# Sheet1.net
KiCad netlist of a schematic drawn in Altium Designer
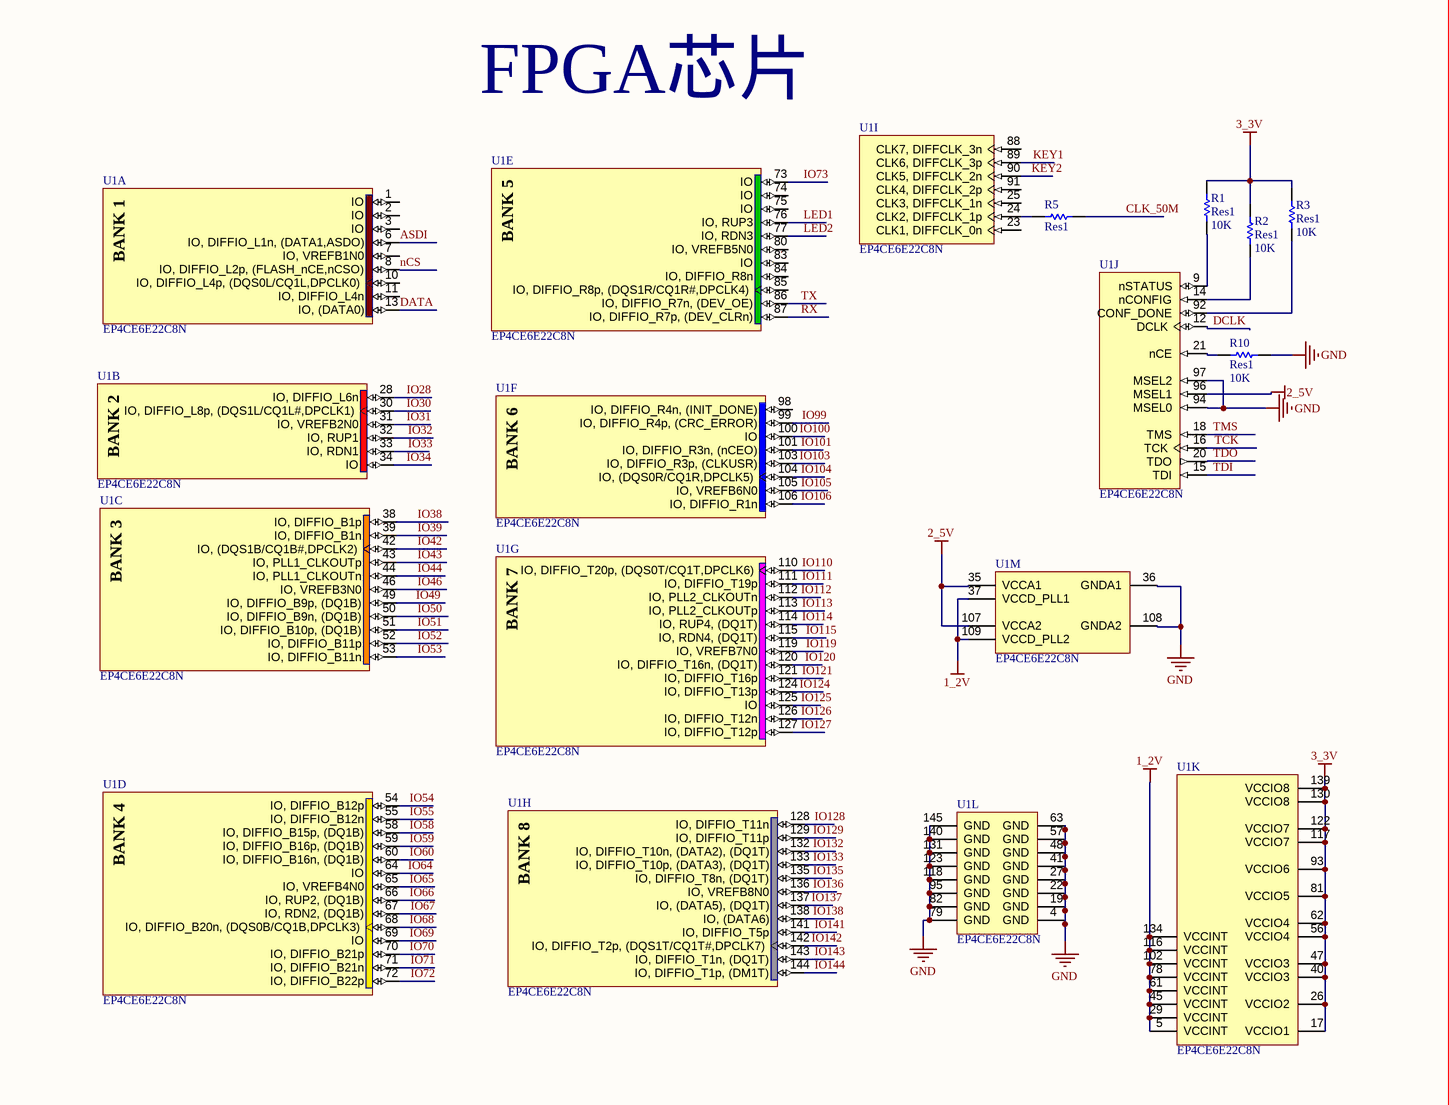
[diagram p0: Sheet1.SchDoc, top left]
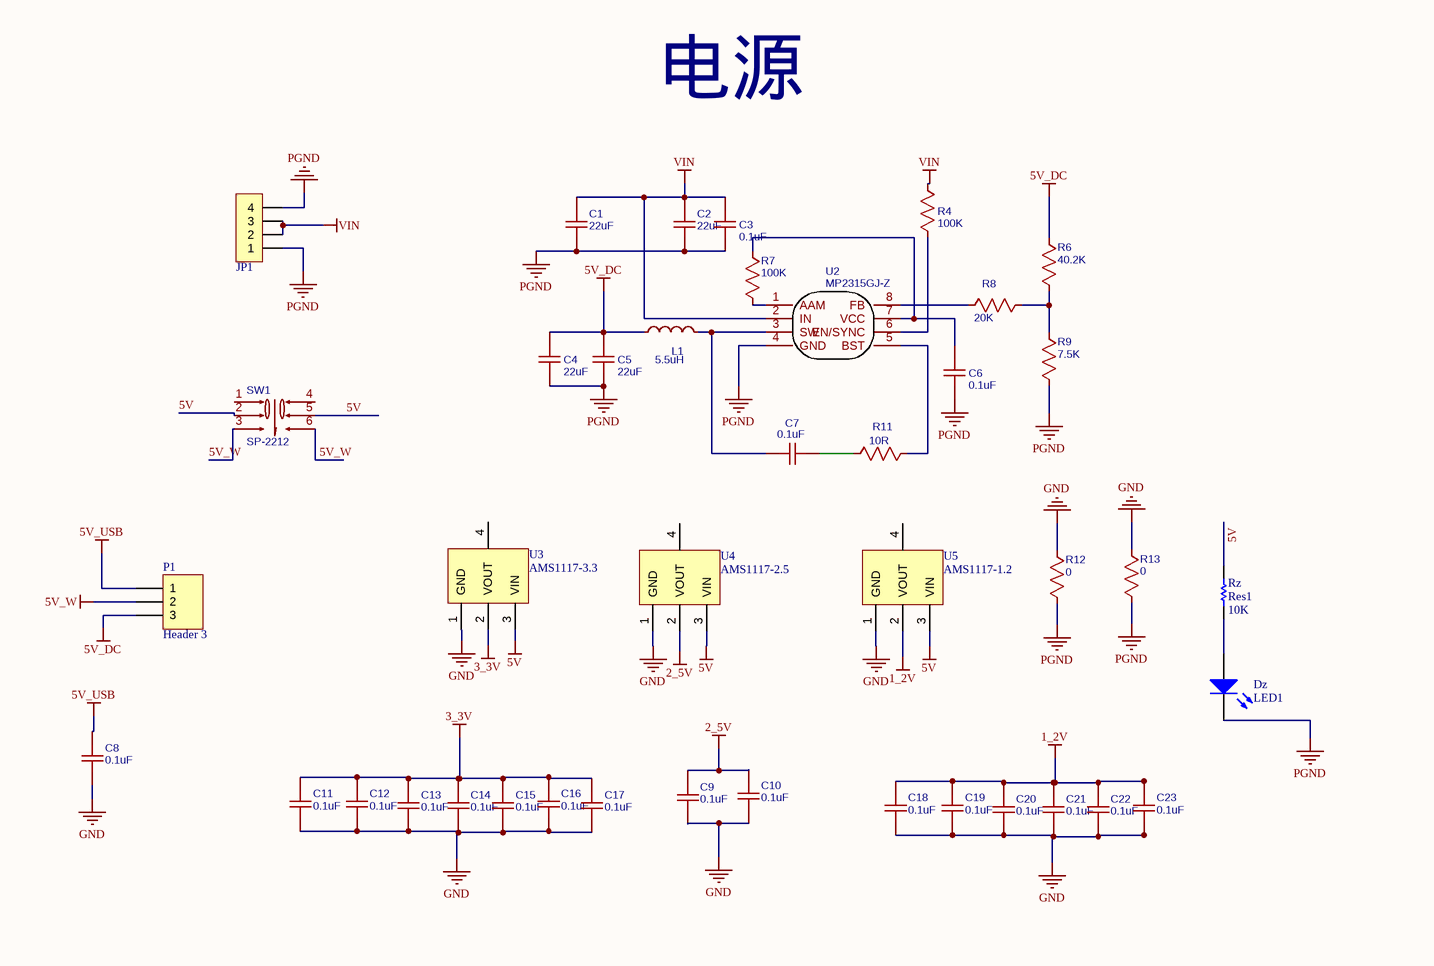
[diagram p1: Sheet1.SchDoc, top right]
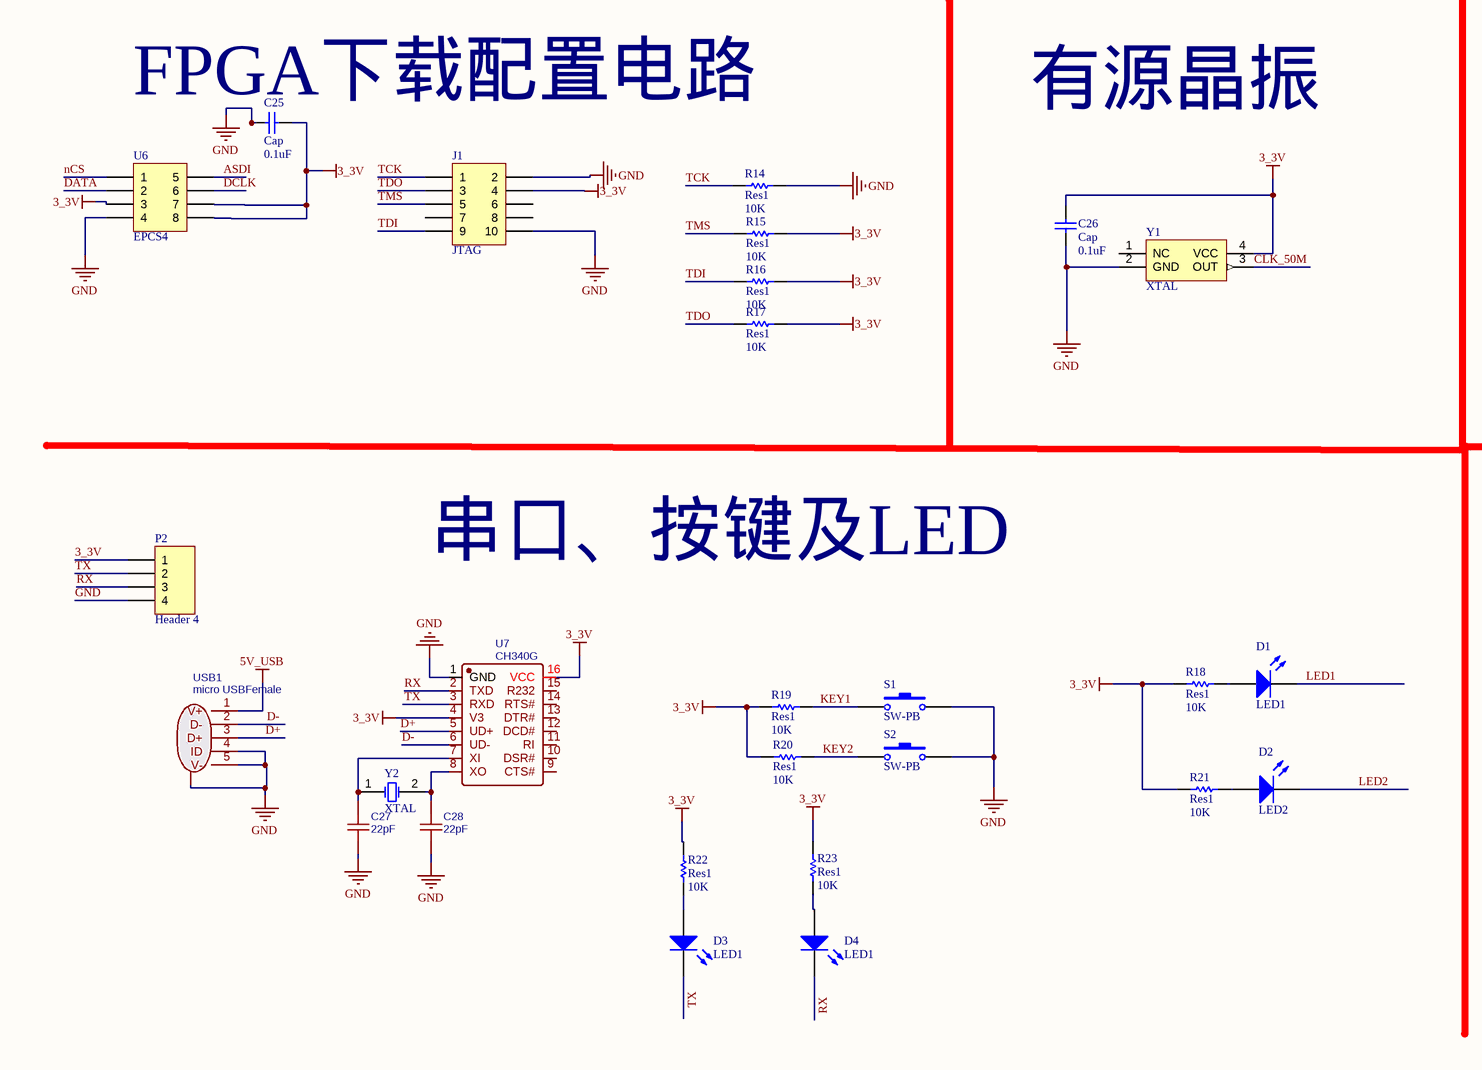
[diagram p2: Sheet1.SchDoc, bottom left]
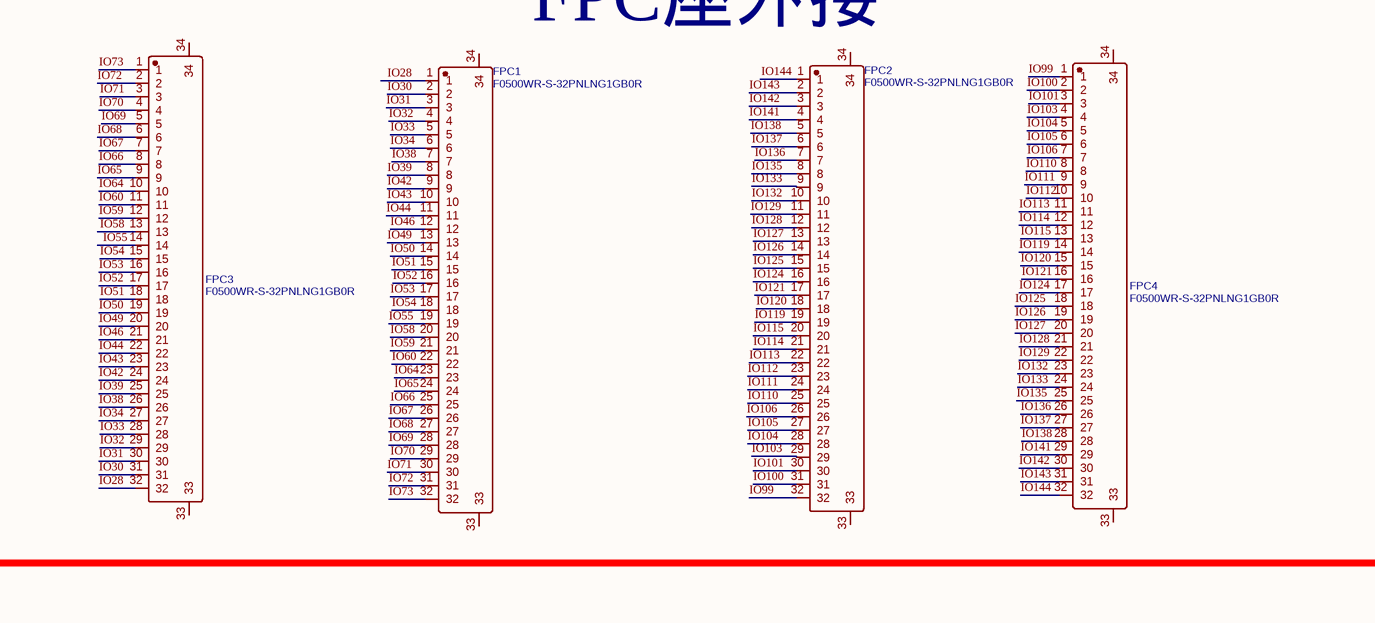
[diagram p3: Sheet1.SchDoc, bottom right]

(export (version "E")
  (design (tool "Eeschema 10.0.6"))
  (components
    (comp (ref "C1")
      (value "22uF")
      (footprint "C 0805_M")
      (fields (field (name "CONTRIBUTOR") "LCEDA_Lib"))
      (libsource (lib "altium-import") (part "root_3_22uF_"))
    )
    (comp (ref "C2")
      (value "22uF")
      (footprint "C 0603_M")
      (fields (field (name "CONTRIBUTOR") "LCEDA_Lib"))
      (libsource (lib "altium-import") (part "root_3_22uF_"))
    )
    (comp (ref "C3")
      (value "0.1uF")
      (footprint "C 0805_M")
      (fields (field (name "CONTRIBUTOR") "LCEDA_Lib"))
      (libsource (lib "altium-import") (part "root_1_0.1uF_"))
    )
    (comp (ref "C4")
      (value "22uF")
      (footprint "C 0805_M")
      (fields (field (name "CONTRIBUTOR") "LCEDA_Lib"))
      (libsource (lib "altium-import") (part "root_1_22uF_"))
    )
    (comp (ref "C5")
      (value "22uF")
      (footprint "C 0805_M")
      (fields (field (name "CONTRIBUTOR") "LCEDA_Lib"))
      (libsource (lib "altium-import") (part "root_1_22uF_"))
    )
    (comp (ref "C6")
      (value "0.1uF")
      (footprint "C 0603_M")
      (fields (field (name "CONTRIBUTOR") "LCEDA_Lib"))
      (libsource (lib "altium-import") (part "root_1_0.1uF_"))
    )
    (comp (ref "C7")
      (value "0.1uF")
      (footprint "C 0805_M")
      (fields (field (name "CONTRIBUTOR") "LCEDA_Lib"))
      (libsource (lib "altium-import") (part "root_0_0.1uF_"))
    )
    (comp (ref "C8")
      (value "0.1uF")
      (footprint "C 0805_M")
      (fields (field (name "CONTRIBUTOR") "LCEDA_Lib"))
      (libsource (lib "altium-import") (part "root_1_0.1uF_"))
    )
    (comp (ref "C9")
      (value "0.1uF")
      (footprint "C 0603_M")
      (fields (field (name "CONTRIBUTOR") "LCEDA_Lib"))
      (libsource (lib "altium-import") (part "root_1_0.1uF_"))
    )
    (comp (ref "C10")
      (value "0.1uF")
      (footprint "C 0603_M")
      (fields (field (name "CONTRIBUTOR") "LCEDA_Lib"))
      (libsource (lib "altium-import") (part "root_1_0.1uF_"))
    )
    (comp (ref "C11")
      (value "0.1uF")
      (footprint "C 0603_M")
      (fields (field (name "CONTRIBUTOR") "LCEDA_Lib"))
      (libsource (lib "altium-import") (part "root_1_0.1uF_"))
    )
    (comp (ref "C12")
      (value "0.1uF")
      (footprint "C 0603_M")
      (fields (field (name "CONTRIBUTOR") "LCEDA_Lib"))
      (libsource (lib "altium-import") (part "root_1_0.1uF_"))
    )
    (comp (ref "C13")
      (value "0.1uF")
      (footprint "C 0603_M")
      (fields (field (name "CONTRIBUTOR") "LCEDA_Lib"))
      (libsource (lib "altium-import") (part "root_1_0.1uF_"))
    )
    (comp (ref "C14")
      (value "0.1uF")
      (footprint "C 0603_M")
      (fields (field (name "CONTRIBUTOR") "LCEDA_Lib"))
      (libsource (lib "altium-import") (part "root_1_0.1uF_"))
    )
    (comp (ref "C15")
      (value "0.1uF")
      (footprint "C 0603_M")
      (fields (field (name "CONTRIBUTOR") "LCEDA_Lib"))
      (libsource (lib "altium-import") (part "root_1_0.1uF_"))
    )
    (comp (ref "C16")
      (value "0.1uF")
      (footprint "C 0603_M")
      (fields (field (name "CONTRIBUTOR") "LCEDA_Lib"))
      (libsource (lib "altium-import") (part "root_1_0.1uF_"))
    )
    (comp (ref "C17")
      (value "0.1uF")
      (footprint "C 0603_M")
      (fields (field (name "CONTRIBUTOR") "LCEDA_Lib"))
      (libsource (lib "altium-import") (part "root_1_0.1uF_"))
    )
    (comp (ref "C18")
      (value "0.1uF")
      (footprint "C 0603_M")
      (fields (field (name "CONTRIBUTOR") "LCEDA_Lib"))
      (libsource (lib "altium-import") (part "root_1_0.1uF_"))
    )
    (comp (ref "C19")
      (value "0.1uF")
      (footprint "C 0603_M")
      (fields (field (name "CONTRIBUTOR") "LCEDA_Lib"))
      (libsource (lib "altium-import") (part "root_1_0.1uF_"))
    )
    (comp (ref "C20")
      (value "0.1uF")
      (footprint "C 0603_M")
      (fields (field (name "CONTRIBUTOR") "LCEDA_Lib"))
      (libsource (lib "altium-import") (part "root_1_0.1uF_"))
    )
    (comp (ref "C21")
      (value "0.1uF")
      (footprint "C 0603_M")
      (fields (field (name "CONTRIBUTOR") "LCEDA_Lib"))
      (libsource (lib "altium-import") (part "root_1_0.1uF_"))
    )
    (comp (ref "C22")
      (value "0.1uF")
      (footprint "C 0603_M")
      (fields (field (name "CONTRIBUTOR") "LCEDA_Lib"))
      (libsource (lib "altium-import") (part "root_1_0.1uF_"))
    )
    (comp (ref "C23")
      (value "0.1uF")
      (footprint "C 0603_M")
      (fields (field (name "CONTRIBUTOR") "LCEDA_Lib"))
      (libsource (lib "altium-import") (part "root_1_0.1uF_"))
    )
    (comp (ref "C25")
      (value "Cap")
      (footprint "C 0805_M")
      (description "Capacitor")
      (fields (field (name "ALTIUM_VALUE") "0.1uF") (field (name "PUBLISHER") "Altium Limited"))
      (libsource (lib "Miscellaneous Devices") (part "Cap"))
    )
    (comp (ref "C26")
      (value "Cap")
      (footprint "C 0805_M")
      (description "Capacitor")
      (fields (field (name "ALTIUM_VALUE") "0.1uF") (field (name "PUBLISHER") "Altium Limited"))
      (libsource (lib "Miscellaneous Devices") (part "Cap"))
    )
    (comp (ref "C27")
      (value "22pF")
      (footprint "C 0603_M")
      (fields (field (name "CONTRIBUTOR") "LCEDA_Lib"))
      (libsource (lib "altium-import") (part "root_1_0.1uF_"))
    )
    (comp (ref "C28")
      (value "22pF")
      (footprint "C 0603_M")
      (fields (field (name "CONTRIBUTOR") "LCEDA_Lib"))
      (libsource (lib "altium-import") (part "root_1_0.1uF_"))
    )
    (comp (ref "D1")
      (value "LED1")
      (footprint "LED-0805")
      (description "Typical INFRARED GaAs LED")
      (fields (field (name "PUBLISHER") "Altium Limited"))
      (libsource (lib "Miscellaneous Devices") (part "LED0"))
    )
    (comp (ref "D2")
      (value "LED2")
      (footprint "LED-0805")
      (description "Typical INFRARED GaAs LED")
      (fields (field (name "PUBLISHER") "Altium Limited"))
      (libsource (lib "Miscellaneous Devices") (part "LED0"))
    )
    (comp (ref "D3")
      (value "LED1")
      (footprint "LED-0805")
      (description "Typical INFRARED GaAs LED")
      (fields (field (name "PUBLISHER") "Altium Limited"))
      (libsource (lib "Miscellaneous Devices") (part "LED0"))
    )
    (comp (ref "D4")
      (value "LED1")
      (footprint "LED-0805")
      (description "Typical INFRARED GaAs LED")
      (fields (field (name "PUBLISHER") "Altium Limited"))
      (libsource (lib "Miscellaneous Devices") (part "LED0"))
    )
    (comp (ref "Dz")
      (value "LED1")
      (footprint "LED-0805")
      (description "Typical INFRARED GaAs LED")
      (fields (field (name "PUBLISHER") "Altium Limited"))
      (libsource (lib "Miscellaneous Devices") (part "LED0"))
    )
    (comp (ref "FPC1")
      (value "F0500WR-S-32PNLNG1GB0R")
      (footprint "FPC0.5 2H-WS-32P")
      (fields (field (name "BOM_SUPPLIER PART") "C247880") (field (name "CONTRIBUTOR") "LCSC"))
      (libsource (lib "altium-import") (part "root_0_F0500WR-S-32PNLNG1GB0R_"))
    )
    (comp (ref "FPC2")
      (value "F0500WR-S-32PNLNG1GB0R")
      (footprint "FPC0.5 2H-WS-32P")
      (fields (field (name "BOM_SUPPLIER PART") "C247880") (field (name "CONTRIBUTOR") "LCSC"))
      (libsource (lib "altium-import") (part "root_0_F0500WR-S-32PNLNG1GB0R_"))
    )
    (comp (ref "FPC3")
      (value "F0500WR-S-32PNLNG1GB0R")
      (footprint "FPC0.5 2H-WS-32P")
      (fields (field (name "BOM_SUPPLIER PART") "C247880") (field (name "CONTRIBUTOR") "LCSC"))
      (libsource (lib "altium-import") (part "root_0_F0500WR-S-32PNLNG1GB0R_"))
    )
    (comp (ref "FPC4")
      (value "F0500WR-S-32PNLNG1GB0R")
      (footprint "FPC0.5 2H-WS-32P")
      (fields (field (name "BOM_SUPPLIER PART") "C247880") (field (name "CONTRIBUTOR") "LCSC"))
      (libsource (lib "altium-import") (part "root_0_F0500WR-S-32PNLNG1GB0R_"))
    )
    (comp (ref "J1")
      (value "JTAG")
      (footprint "牛角座10p")
      (description "Header, 5-Pin, Dual row, Right Angle")
      (fields (field (name "PUBLISHER") "Altium Limited"))
      (libsource (lib "Miscellaneous Connectors") (part "Header 5X2H"))
    )
    (comp (ref "JP1")
      (value "HDR-1X4")
      (footprint "KF128-5.08-4P")
      (description "4P接插件")
      (fields (field (name "版权归属") "封装库来自淘宝卖家 ID：黄晶宝石"))
      (libsource (lib "6.1 - 接插件-脚距5.08 (200mil) ") (part "Header 4"))
    )
    (comp (ref "L1")
      (value "5.5uH")
      (footprint "L-SMD-0630")
      (fields
        (field (name "BOM_SUPPLIER PART") "C268387")
        (field (name "BOM_MANUFACTURER PART") "MPCA-0624-4R7-M")
        (field (name "CONTRIBUTOR") "LCSC")
      )
      (libsource (lib "altium-import") (part "root_0_4.7uH_"))
    )
    (comp (ref "P1")
      (value "Header 3")
      (footprint "HDR1X3")
      (description "Header, 3-Pin")
      (fields (field (name "PUBLISHER") "Altium Limited"))
      (libsource (lib "Miscellaneous Connectors") (part "Header 3"))
    )
    (comp (ref "P2")
      (value "Header 4")
      (footprint "HDR1X4")
      (description "Header, 4-Pin")
      (fields (field (name "PUBLISHER") "Altium Limited"))
      (libsource (lib "Miscellaneous Connectors") (part "Header 4"))
    )
    (comp (ref "R1")
      (value "Res1")
      (footprint "R 0603_M")
      (description "Resistor")
      (fields (field (name "ALTIUM_VALUE") "10K") (field (name "PUBLISHER") "Altium Limited"))
      (libsource (lib "Miscellaneous Devices") (part "Res1"))
    )
    (comp (ref "R2")
      (value "Res1")
      (footprint "R 0603_M")
      (description "Resistor")
      (fields (field (name "ALTIUM_VALUE") "10K") (field (name "PUBLISHER") "Altium Limited"))
      (libsource (lib "Miscellaneous Devices") (part "Res1"))
    )
    (comp (ref "R3")
      (value "Res1")
      (footprint "R 0603_M")
      (description "Resistor")
      (fields (field (name "ALTIUM_VALUE") "10K") (field (name "PUBLISHER") "Altium Limited"))
      (libsource (lib "Miscellaneous Devices") (part "Res1"))
    )
    (comp (ref "R4")
      (value "100K")
      (footprint "R 0603_M")
      (fields (field (name "CONTRIBUTOR") "LCEDA_Lib"))
      (libsource (lib "altium-import") (part "root_1_100K_"))
    )
    (comp (ref "R5")
      (value "Res1")
      (footprint "R 0603_M")
      (description "Resistor")
      (fields (field (name "PUBLISHER") "Altium Limited"))
      (libsource (lib "Miscellaneous Devices") (part "Res1"))
    )
    (comp (ref "R6")
      (value "40.2K")
      (footprint "R 0603_M")
      (fields (field (name "CONTRIBUTOR") "LCEDA_Lib"))
      (libsource (lib "altium-import") (part "root_3_10R_"))
    )
    (comp (ref "R7")
      (value "100K")
      (footprint "R 0603_M")
      (fields (field (name "CONTRIBUTOR") "LCEDA_Lib"))
      (libsource (lib "altium-import") (part "root_3_7.5k_"))
    )
    (comp (ref "R8")
      (value "20K")
      (footprint "R 0603_M")
      (fields (field (name "CONTRIBUTOR") "LCEDA_Lib"))
      (libsource (lib "altium-import") (part "root_2_10R_"))
    )
    (comp (ref "R9")
      (value "7.5K")
      (footprint "R 0603_M")
      (fields (field (name "CONTRIBUTOR") "LCEDA_Lib"))
      (libsource (lib "altium-import") (part "root_3_10R_"))
    )
    (comp (ref "R10")
      (value "Res1")
      (footprint "R 0603_M")
      (description "Resistor")
      (fields (field (name "ALTIUM_VALUE") "10K") (field (name "PUBLISHER") "Altium Limited"))
      (libsource (lib "Miscellaneous Devices") (part "Res1"))
    )
    (comp (ref "R11")
      (value "10R")
      (footprint "R 0603_M")
      (fields (field (name "CONTRIBUTOR") "LCEDA_Lib"))
      (libsource (lib "altium-import") (part "root_2_10R_"))
    )
    (comp (ref "R12")
      (value "0")
      (footprint "R 0603_M")
      (fields (field (name "CONTRIBUTOR") "LCEDA_Lib"))
      (libsource (lib "altium-import") (part "root_3_10R_"))
    )
    (comp (ref "R13")
      (value "0")
      (footprint "R 0603_M")
      (fields (field (name "CONTRIBUTOR") "LCEDA_Lib"))
      (libsource (lib "altium-import") (part "root_3_10R_"))
    )
    (comp (ref "R14")
      (value "Res1")
      (footprint "R 0603_M")
      (description "Resistor")
      (fields (field (name "ALTIUM_VALUE") "10K") (field (name "PUBLISHER") "Altium Limited"))
      (libsource (lib "Miscellaneous Devices") (part "Res1"))
    )
    (comp (ref "R15")
      (value "Res1")
      (footprint "R 0603_M")
      (description "Resistor")
      (fields (field (name "ALTIUM_VALUE") "10K") (field (name "PUBLISHER") "Altium Limited"))
      (libsource (lib "Miscellaneous Devices") (part "Res1"))
    )
    (comp (ref "R16")
      (value "Res1")
      (footprint "R 0603_M")
      (description "Resistor")
      (fields (field (name "ALTIUM_VALUE") "10K") (field (name "PUBLISHER") "Altium Limited"))
      (libsource (lib "Miscellaneous Devices") (part "Res1"))
    )
    (comp (ref "R17")
      (value "Res1")
      (footprint "R 0603_M")
      (description "Resistor")
      (fields (field (name "ALTIUM_VALUE") "10K") (field (name "PUBLISHER") "Altium Limited"))
      (libsource (lib "Miscellaneous Devices") (part "Res1"))
    )
    (comp (ref "R18")
      (value "Res1")
      (footprint "R 0603_M")
      (description "Resistor")
      (fields (field (name "ALTIUM_VALUE") "10K") (field (name "PUBLISHER") "Altium Limited"))
      (libsource (lib "Miscellaneous Devices") (part "Res1"))
    )
    (comp (ref "R19")
      (value "Res1")
      (footprint "R 0603_M")
      (description "Resistor")
      (fields (field (name "ALTIUM_VALUE") "10K") (field (name "PUBLISHER") "Altium Limited"))
      (libsource (lib "Miscellaneous Devices") (part "Res1"))
    )
    (comp (ref "R20")
      (value "Res1")
      (footprint "R 0603_M")
      (description "Resistor")
      (fields (field (name "ALTIUM_VALUE") "10K") (field (name "PUBLISHER") "Altium Limited"))
      (libsource (lib "Miscellaneous Devices") (part "Res1"))
    )
    (comp (ref "R21")
      (value "Res1")
      (footprint "R 0603_M")
      (description "Resistor")
      (fields (field (name "ALTIUM_VALUE") "10K") (field (name "PUBLISHER") "Altium Limited"))
      (libsource (lib "Miscellaneous Devices") (part "Res1"))
    )
    (comp (ref "R22")
      (value "Res1")
      (footprint "R 0603_M")
      (description "Resistor")
      (fields (field (name "ALTIUM_VALUE") "10K") (field (name "PUBLISHER") "Altium Limited"))
      (libsource (lib "Miscellaneous Devices") (part "Res1"))
    )
    (comp (ref "R23")
      (value "Res1")
      (footprint "R 0603_M")
      (description "Resistor")
      (fields (field (name "ALTIUM_VALUE") "10K") (field (name "PUBLISHER") "Altium Limited"))
      (libsource (lib "Miscellaneous Devices") (part "Res1"))
    )
    (comp (ref "Rz")
      (value "Res1")
      (footprint "R 0603_M")
      (description "Resistor")
      (fields (field (name "ALTIUM_VALUE") "10K") (field (name "PUBLISHER") "Altium Limited"))
      (libsource (lib "Miscellaneous Devices") (part "Res1"))
    )
    (comp (ref "S1")
      (value "SW-PB")
      (footprint "SPST4")
      (description "Switch")
      (fields (field (name "PUBLISHER") "Altium Limited"))
      (libsource (lib "我的元件库") (part "SW-PB"))
    )
    (comp (ref "S2")
      (value "SW-PB")
      (footprint "SPST4")
      (description "Switch")
      (fields (field (name "PUBLISHER") "Altium Limited"))
      (libsource (lib "我的元件库") (part "SW-PB"))
    )
    (comp (ref "SW1")
      (value "SP-2212")
      (footprint "自锁开关")
      (fields (field (name "BOM_SUPPLIER PART") "C589287") (field (name "CONTRIBUTOR") "LCSC"))
      (libsource (lib "altium-import") (part "root_3_SP-2212_"))
    )
    (comp (ref "U1")
      (value "EP4CE6E22C8N")
      (footprint "EQFP144_A-165_D2-54_N")
      (fields (field (name "MANUFACTURER") "Altera"))
      (libsource (lib "Altera Cyclone IV E") (part "EP4CE6E22C8N"))
    )
    (comp (ref "U2")
      (value "MP2315GJ-Z")
      (footprint "SOT23-8N")
      (fields (field (name "BOM_SUPPLIER PART") "C45889"))
      (libsource (lib "altium-import") (part "root_0_MP2315GJ-Z_"))
    )
    (comp (ref "U3")
      (value "AMS1117-3.3")
      (footprint "SOT223_N")
      (description "3.3Voutput,4.3-12Vinput LDO")
      (libsource (lib "我的元件库") (part "AMS1117"))
    )
    (comp (ref "U4")
      (value "AMS1117-2.5")
      (footprint "SOT223_N")
      (description "3.3Voutput,4.3-12Vinput LDO")
      (libsource (lib "我的元件库") (part "AMS1117"))
    )
    (comp (ref "U5")
      (value "AMS1117-1.2")
      (footprint "SOT223_N")
      (description "3.3Voutput,4.3-12Vinput LDO")
      (libsource (lib "我的元件库") (part "AMS1117"))
    )
    (comp (ref "U6")
      (value "EPCS4")
      (footprint "SOP8")
      (description "Header, 4-Pin, Dual row")
      (fields (field (name "PUBLISHER") "Altium Limited"))
      (libsource (lib "Miscellaneous Connectors") (part "Header 4X2A"))
    )
    (comp (ref "U7")
      (value "CH340G")
      (footprint "SOIC-16_L9.9-W3.9-P1.27-LS6.0-BL")
      (fields (field (name "BOM_SUPPLIER PART") "C14267"))
      (libsource (lib "altium-import") (part "root_0_CH340G_"))
    )
    (comp (ref "USB1")
      (value "micro USBFemale")
      (footprint "MICRO-USB-SMD_5P-P0.65-H-F_C10418")
      (fields (field (name "BOM_SUPPLIER PART") "C10418"))
      (libsource (lib "altium-import") (part "root_0_micro USBFemale_"))
    )
    (comp (ref "Y1")
      (value "XTAL")
      (footprint "OSC-SMD_4P-L7.0-W5.0-BL")
      (libsource (lib "我的元件库") (part "有源晶振"))
    )
    (comp (ref "Y2")
      (value "XTAL")
      (footprint "标准晶振")
      (description "Crystal Oscillator")
      (fields (field (name "PUBLISHER") "Altium Limited"))
      (libsource (lib "Miscellaneous Devices") (part "XTAL"))
    )
  )
  (nets
    (net (code "1") (name "/ASDI") (class "Default")
      (node (ref "U1") (pin "6") (pinfunction "IO,_DIFFIO_L1n,_(DATA1,ASDO)_6") (pintype "bidirectional"))
      (node (ref "U6") (pin "5") (pinfunction "5_5") (pintype "passive"))
    )
    (net (code "2") (name "/CLK_50M") (class "Default")
      (node (ref "R5") (pin "2") (pinfunction "2_2") (pintype "passive"))
      (node (ref "Y1") (pin "3") (pinfunction "OUT_3") (pintype "output"))
    )
    (net (code "3") (name "/D+") (class "Default")
      (node (ref "U7") (pin "5") (pinfunction "UD+_5") (pintype "passive"))
      (node (ref "USB1") (pin "3") (pinfunction "D+_3") (pintype "passive"))
    )
    (net (code "4") (name "/D-") (class "Default")
      (node (ref "U7") (pin "6") (pinfunction "UD-_6") (pintype "passive"))
      (node (ref "USB1") (pin "2") (pinfunction "D-_2") (pintype "passive"))
    )
    (net (code "5") (name "/DATA") (class "Default")
      (node (ref "U1") (pin "13") (pinfunction "IO,_(DATA0)_13") (pintype "bidirectional"))
      (node (ref "U6") (pin "2") (pinfunction "2_2") (pintype "passive"))
    )
    (net (code "6") (name "/DCLK") (class "Default")
      (node (ref "U1") (pin "12") (pinfunction "DCLK_12") (pintype "bidirectional"))
      (node (ref "U6") (pin "6") (pinfunction "6_6") (pintype "passive"))
    )
    (net (code "7") (name "/IO28") (class "Default")
      (node (ref "FPC1") (pin "1") (pinfunction "1_1") (pintype "passive"))
      (node (ref "FPC3") (pin "32") (pinfunction "32_32") (pintype "passive"))
      (node (ref "U1") (pin "28") (pinfunction "IO,_DIFFIO_L6n_28") (pintype "bidirectional"))
    )
    (net (code "8") (name "/IO30") (class "Default")
      (node (ref "FPC1") (pin "2") (pinfunction "2_2") (pintype "passive"))
      (node (ref "FPC3") (pin "31") (pinfunction "31_31") (pintype "passive"))
      (node (ref "U1") (pin "30") (pinfunction "IO,_DIFFIO_L8p,_(DQS1L/CQ1L#,DPCLK1)_30") (pintype "bidirectional"))
    )
    (net (code "9") (name "/IO31") (class "Default")
      (node (ref "FPC1") (pin "3") (pinfunction "3_3") (pintype "passive"))
      (node (ref "FPC3") (pin "30") (pinfunction "30_30") (pintype "passive"))
      (node (ref "U1") (pin "31") (pinfunction "IO,_VREFB2N0_31") (pintype "bidirectional"))
    )
    (net (code "10") (name "/IO32") (class "Default")
      (node (ref "FPC1") (pin "4") (pinfunction "4_4") (pintype "passive"))
      (node (ref "FPC3") (pin "29") (pinfunction "29_29") (pintype "passive"))
      (node (ref "U1") (pin "32") (pinfunction "IO,_RUP1_32") (pintype "bidirectional"))
    )
    (net (code "11") (name "/IO33") (class "Default")
      (node (ref "FPC1") (pin "5") (pinfunction "5_5") (pintype "passive"))
      (node (ref "FPC3") (pin "28") (pinfunction "28_28") (pintype "passive"))
      (node (ref "U1") (pin "33") (pinfunction "IO,_RDN1_33") (pintype "bidirectional"))
    )
    (net (code "12") (name "/IO34") (class "Default")
      (node (ref "FPC1") (pin "6") (pinfunction "6_6") (pintype "passive"))
      (node (ref "FPC3") (pin "27") (pinfunction "27_27") (pintype "passive"))
      (node (ref "U1") (pin "34") (pinfunction "IO_34") (pintype "bidirectional"))
    )
    (net (code "13") (name "/IO38") (class "Default")
      (node (ref "FPC1") (pin "7") (pinfunction "7_7") (pintype "passive"))
      (node (ref "FPC3") (pin "26") (pinfunction "26_26") (pintype "passive"))
      (node (ref "U1") (pin "38") (pinfunction "IO,_DIFFIO_B1p_38") (pintype "bidirectional"))
    )
    (net (code "14") (name "/IO39") (class "Default")
      (node (ref "FPC1") (pin "8") (pinfunction "8_8") (pintype "passive"))
      (node (ref "FPC3") (pin "25") (pinfunction "25_25") (pintype "passive"))
      (node (ref "U1") (pin "39") (pinfunction "IO,_DIFFIO_B1n_39") (pintype "bidirectional"))
    )
    (net (code "15") (name "/IO42") (class "Default")
      (node (ref "FPC1") (pin "9") (pinfunction "9_9") (pintype "passive"))
      (node (ref "FPC3") (pin "24") (pinfunction "24_24") (pintype "passive"))
      (node (ref "U1") (pin "42") (pinfunction "IO,_(DQS1B/CQ1B#,DPCLK2)_42") (pintype "bidirectional"))
    )
    (net (code "16") (name "/IO43") (class "Default")
      (node (ref "FPC1") (pin "10") (pinfunction "10_10") (pintype "passive"))
      (node (ref "FPC3") (pin "23") (pinfunction "23_23") (pintype "passive"))
      (node (ref "U1") (pin "43") (pinfunction "IO,_PLL1_CLKOUTp_43") (pintype "bidirectional"))
    )
    (net (code "17") (name "/IO44") (class "Default")
      (node (ref "FPC1") (pin "11") (pinfunction "11_11") (pintype "passive"))
      (node (ref "FPC3") (pin "22") (pinfunction "22_22") (pintype "passive"))
      (node (ref "U1") (pin "44") (pinfunction "IO,_PLL1_CLKOUTn_44") (pintype "bidirectional"))
    )
    (net (code "18") (name "/IO46") (class "Default")
      (node (ref "FPC1") (pin "12") (pinfunction "12_12") (pintype "passive"))
      (node (ref "FPC3") (pin "21") (pinfunction "21_21") (pintype "passive"))
      (node (ref "U1") (pin "46") (pinfunction "IO,_VREFB3N0_46") (pintype "bidirectional"))
    )
    (net (code "19") (name "/IO49") (class "Default")
      (node (ref "FPC1") (pin "13") (pinfunction "13_13") (pintype "passive"))
      (node (ref "FPC3") (pin "20") (pinfunction "20_20") (pintype "passive"))
      (node (ref "U1") (pin "49") (pinfunction "IO,_DIFFIO_B9p,_(DQ1B)_49") (pintype "bidirectional"))
    )
    (net (code "20") (name "/IO50") (class "Default")
      (node (ref "FPC1") (pin "14") (pinfunction "14_14") (pintype "passive"))
      (node (ref "FPC3") (pin "19") (pinfunction "19_19") (pintype "passive"))
      (node (ref "U1") (pin "50") (pinfunction "IO,_DIFFIO_B9n,_(DQ1B)_50") (pintype "bidirectional"))
    )
    (net (code "21") (name "/IO51") (class "Default")
      (node (ref "FPC1") (pin "15") (pinfunction "15_15") (pintype "passive"))
      (node (ref "FPC3") (pin "18") (pinfunction "18_18") (pintype "passive"))
      (node (ref "U1") (pin "51") (pinfunction "IO,_DIFFIO_B10p,_(DQ1B)_51") (pintype "bidirectional"))
    )
    (net (code "22") (name "/IO52") (class "Default")
      (node (ref "FPC1") (pin "16") (pinfunction "16_16") (pintype "passive"))
      (node (ref "FPC3") (pin "17") (pinfunction "17_17") (pintype "passive"))
      (node (ref "U1") (pin "52") (pinfunction "IO,_DIFFIO_B11p_52") (pintype "bidirectional"))
    )
    (net (code "23") (name "/IO53") (class "Default")
      (node (ref "FPC1") (pin "17") (pinfunction "17_17") (pintype "passive"))
      (node (ref "FPC3") (pin "16") (pinfunction "16_16") (pintype "passive"))
      (node (ref "U1") (pin "53") (pinfunction "IO,_DIFFIO_B11n_53") (pintype "bidirectional"))
    )
    (net (code "24") (name "/IO54") (class "Default")
      (node (ref "FPC1") (pin "18") (pinfunction "18_18") (pintype "passive"))
      (node (ref "FPC3") (pin "15") (pinfunction "15_15") (pintype "passive"))
      (node (ref "U1") (pin "54") (pinfunction "IO,_DIFFIO_B12p_54") (pintype "bidirectional"))
    )
    (net (code "25") (name "/IO55") (class "Default")
      (node (ref "FPC1") (pin "19") (pinfunction "19_19") (pintype "passive"))
      (node (ref "FPC3") (pin "14") (pinfunction "14_14") (pintype "passive"))
      (node (ref "U1") (pin "55") (pinfunction "IO,_DIFFIO_B12n_55") (pintype "bidirectional"))
    )
    (net (code "26") (name "/IO58") (class "Default")
      (node (ref "FPC1") (pin "20") (pinfunction "20_20") (pintype "passive"))
      (node (ref "FPC3") (pin "13") (pinfunction "13_13") (pintype "passive"))
      (node (ref "U1") (pin "58") (pinfunction "IO,_DIFFIO_B15p,_(DQ1B)_58") (pintype "bidirectional"))
    )
    (net (code "27") (name "/IO59") (class "Default")
      (node (ref "FPC1") (pin "21") (pinfunction "21_21") (pintype "passive"))
      (node (ref "FPC3") (pin "12") (pinfunction "12_12") (pintype "passive"))
      (node (ref "U1") (pin "59") (pinfunction "IO,_DIFFIO_B16p,_(DQ1B)_59") (pintype "bidirectional"))
    )
    (net (code "28") (name "/IO60") (class "Default")
      (node (ref "FPC1") (pin "22") (pinfunction "22_22") (pintype "passive"))
      (node (ref "FPC3") (pin "11") (pinfunction "11_11") (pintype "passive"))
      (node (ref "U1") (pin "60") (pinfunction "IO,_DIFFIO_B16n,_(DQ1B)_60") (pintype "bidirectional"))
    )
    (net (code "29") (name "/IO64") (class "Default")
      (node (ref "FPC1") (pin "23") (pinfunction "23_23") (pintype "passive"))
      (node (ref "FPC3") (pin "10") (pinfunction "10_10") (pintype "passive"))
      (node (ref "U1") (pin "64") (pinfunction "IO_64") (pintype "bidirectional"))
    )
    (net (code "30") (name "/IO65") (class "Default")
      (node (ref "FPC1") (pin "24") (pinfunction "24_24") (pintype "passive"))
      (node (ref "FPC3") (pin "9") (pinfunction "9_9") (pintype "passive"))
      (node (ref "U1") (pin "65") (pinfunction "IO,_VREFB4N0_65") (pintype "bidirectional"))
    )
    (net (code "31") (name "/IO66") (class "Default")
      (node (ref "FPC1") (pin "25") (pinfunction "25_25") (pintype "passive"))
      (node (ref "FPC3") (pin "8") (pinfunction "8_8") (pintype "passive"))
      (node (ref "U1") (pin "66") (pinfunction "IO,_RUP2,_(DQ1B)_66") (pintype "bidirectional"))
    )
    (net (code "32") (name "/IO67") (class "Default")
      (node (ref "FPC1") (pin "26") (pinfunction "26_26") (pintype "passive"))
      (node (ref "FPC3") (pin "7") (pinfunction "7_7") (pintype "passive"))
      (node (ref "U1") (pin "67") (pinfunction "IO,_RDN2,_(DQ1B)_67") (pintype "bidirectional"))
    )
    (net (code "33") (name "/IO68") (class "Default")
      (node (ref "FPC1") (pin "27") (pinfunction "27_27") (pintype "passive"))
      (node (ref "FPC3") (pin "6") (pinfunction "6_6") (pintype "passive"))
      (node (ref "U1") (pin "68") (pinfunction "IO,_DIFFIO_B20n,_(DQS0B/CQ1B,DPCLK3)_68") (pintype "bidirectional"))
    )
    (net (code "34") (name "/IO69") (class "Default")
      (node (ref "FPC1") (pin "28") (pinfunction "28_28") (pintype "passive"))
      (node (ref "FPC3") (pin "5") (pinfunction "5_5") (pintype "passive"))
      (node (ref "U1") (pin "69") (pinfunction "IO_69") (pintype "bidirectional"))
    )
    (net (code "35") (name "/IO70") (class "Default")
      (node (ref "FPC1") (pin "29") (pinfunction "29_29") (pintype "passive"))
      (node (ref "FPC3") (pin "4") (pinfunction "4_4") (pintype "passive"))
      (node (ref "U1") (pin "70") (pinfunction "IO,_DIFFIO_B21p_70") (pintype "bidirectional"))
    )
    (net (code "36") (name "/IO71") (class "Default")
      (node (ref "FPC1") (pin "30") (pinfunction "30_30") (pintype "passive"))
      (node (ref "FPC3") (pin "3") (pinfunction "3_3") (pintype "passive"))
      (node (ref "U1") (pin "71") (pinfunction "IO,_DIFFIO_B21n_71") (pintype "bidirectional"))
    )
    (net (code "37") (name "/IO72") (class "Default")
      (node (ref "FPC1") (pin "31") (pinfunction "31_31") (pintype "passive"))
      (node (ref "FPC3") (pin "2") (pinfunction "2_2") (pintype "passive"))
      (node (ref "U1") (pin "72") (pinfunction "IO,_DIFFIO_B22p_72") (pintype "bidirectional"))
    )
    (net (code "38") (name "/IO73") (class "Default")
      (node (ref "FPC1") (pin "32") (pinfunction "32_32") (pintype "passive"))
      (node (ref "FPC3") (pin "1") (pinfunction "1_1") (pintype "passive"))
      (node (ref "U1") (pin "73") (pinfunction "IO_73") (pintype "bidirectional"))
    )
    (net (code "39") (name "/IO99") (class "Default")
      (node (ref "FPC2") (pin "32") (pinfunction "32_32") (pintype "passive"))
      (node (ref "FPC4") (pin "1") (pinfunction "1_1") (pintype "passive"))
      (node (ref "U1") (pin "99") (pinfunction "IO,_DIFFIO_R4p,_(CRC_ERROR)_99") (pintype "bidirectional"))
    )
    (net (code "40") (name "/IO100") (class "Default")
      (node (ref "FPC2") (pin "31") (pinfunction "31_31") (pintype "passive"))
      (node (ref "FPC4") (pin "2") (pinfunction "2_2") (pintype "passive"))
      (node (ref "U1") (pin "100") (pinfunction "IO_100") (pintype "bidirectional"))
    )
    (net (code "41") (name "/IO101") (class "Default")
      (node (ref "FPC2") (pin "30") (pinfunction "30_30") (pintype "passive"))
      (node (ref "FPC4") (pin "3") (pinfunction "3_3") (pintype "passive"))
      (node (ref "U1") (pin "101") (pinfunction "IO,_DIFFIO_R3n,_(nCEO)_101") (pintype "bidirectional"))
    )
    (net (code "42") (name "/IO103") (class "Default")
      (node (ref "FPC2") (pin "29") (pinfunction "29_29") (pintype "passive"))
      (node (ref "FPC4") (pin "4") (pinfunction "4_4") (pintype "passive"))
      (node (ref "U1") (pin "103") (pinfunction "IO,_DIFFIO_R3p,_(CLKUSR)_103") (pintype "bidirectional"))
    )
    (net (code "43") (name "/IO104") (class "Default")
      (node (ref "FPC2") (pin "28") (pinfunction "28_28") (pintype "passive"))
      (node (ref "FPC4") (pin "5") (pinfunction "5_5") (pintype "passive"))
      (node (ref "U1") (pin "104") (pinfunction "IO,_(DQS0R/CQ1R,DPCLK5)_104") (pintype "bidirectional"))
    )
    (net (code "44") (name "/IO105") (class "Default")
      (node (ref "FPC2") (pin "27") (pinfunction "27_27") (pintype "passive"))
      (node (ref "FPC4") (pin "6") (pinfunction "6_6") (pintype "passive"))
      (node (ref "U1") (pin "105") (pinfunction "IO,_VREFB6N0_105") (pintype "bidirectional"))
    )
    (net (code "45") (name "/IO106") (class "Default")
      (node (ref "FPC2") (pin "26") (pinfunction "26_26") (pintype "passive"))
      (node (ref "FPC4") (pin "7") (pinfunction "7_7") (pintype "passive"))
      (node (ref "U1") (pin "106") (pinfunction "IO,_DIFFIO_R1n_106") (pintype "bidirectional"))
    )
    (net (code "46") (name "/IO110") (class "Default")
      (node (ref "FPC2") (pin "25") (pinfunction "25_25") (pintype "passive"))
      (node (ref "FPC4") (pin "8") (pinfunction "8_8") (pintype "passive"))
      (node (ref "U1") (pin "110") (pinfunction "IO,_DIFFIO_T20p,_(DQS0T/CQ1T,DPCLK6)_110") (pintype "bidirectional"))
    )
    (net (code "47") (name "/IO111") (class "Default")
      (node (ref "FPC2") (pin "24") (pinfunction "24_24") (pintype "passive"))
      (node (ref "FPC4") (pin "9") (pinfunction "9_9") (pintype "passive"))
      (node (ref "U1") (pin "111") (pinfunction "IO,_DIFFIO_T19p_111") (pintype "bidirectional"))
    )
    (net (code "48") (name "/IO112") (class "Default")
      (node (ref "FPC2") (pin "23") (pinfunction "23_23") (pintype "passive"))
      (node (ref "FPC4") (pin "10") (pinfunction "10_10") (pintype "passive"))
      (node (ref "U1") (pin "112") (pinfunction "IO,_PLL2_CLKOUTn_112") (pintype "bidirectional"))
    )
    (net (code "49") (name "/IO113") (class "Default")
      (node (ref "FPC2") (pin "22") (pinfunction "22_22") (pintype "passive"))
      (node (ref "FPC4") (pin "11") (pinfunction "11_11") (pintype "passive"))
      (node (ref "U1") (pin "113") (pinfunction "IO,_PLL2_CLKOUTp_113") (pintype "bidirectional"))
    )
    (net (code "50") (name "/IO114") (class "Default")
      (node (ref "FPC2") (pin "21") (pinfunction "21_21") (pintype "passive"))
      (node (ref "FPC4") (pin "12") (pinfunction "12_12") (pintype "passive"))
      (node (ref "U1") (pin "114") (pinfunction "IO,_RUP4,_(DQ1T)_114") (pintype "bidirectional"))
    )
    (net (code "51") (name "/IO115") (class "Default")
      (node (ref "FPC2") (pin "20") (pinfunction "20_20") (pintype "passive"))
      (node (ref "FPC4") (pin "13") (pinfunction "13_13") (pintype "passive"))
      (node (ref "U1") (pin "115") (pinfunction "IO,_RDN4,_(DQ1T)_115") (pintype "bidirectional"))
    )
    (net (code "52") (name "/IO119") (class "Default")
      (node (ref "FPC2") (pin "19") (pinfunction "19_19") (pintype "passive"))
      (node (ref "FPC4") (pin "14") (pinfunction "14_14") (pintype "passive"))
      (node (ref "U1") (pin "119") (pinfunction "IO,_VREFB7N0_119") (pintype "bidirectional"))
    )
    (net (code "53") (name "/IO120") (class "Default")
      (node (ref "FPC2") (pin "18") (pinfunction "18_18") (pintype "passive"))
      (node (ref "FPC4") (pin "15") (pinfunction "15_15") (pintype "passive"))
      (node (ref "U1") (pin "120") (pinfunction "IO,_DIFFIO_T16n,_(DQ1T)_120") (pintype "bidirectional"))
    )
    (net (code "54") (name "/IO121") (class "Default")
      (node (ref "FPC2") (pin "17") (pinfunction "17_17") (pintype "passive"))
      (node (ref "FPC4") (pin "16") (pinfunction "16_16") (pintype "passive"))
      (node (ref "U1") (pin "121") (pinfunction "IO,_DIFFIO_T16p_121") (pintype "bidirectional"))
    )
    (net (code "55") (name "/IO124") (class "Default")
      (node (ref "FPC2") (pin "16") (pinfunction "16_16") (pintype "passive"))
      (node (ref "FPC4") (pin "17") (pinfunction "17_17") (pintype "passive"))
      (node (ref "U1") (pin "124") (pinfunction "IO,_DIFFIO_T13p_124") (pintype "bidirectional"))
    )
    (net (code "56") (name "/IO125") (class "Default")
      (node (ref "FPC2") (pin "15") (pinfunction "15_15") (pintype "passive"))
      (node (ref "FPC4") (pin "18") (pinfunction "18_18") (pintype "passive"))
      (node (ref "U1") (pin "125") (pinfunction "IO_125") (pintype "bidirectional"))
    )
    (net (code "57") (name "/IO126") (class "Default")
      (node (ref "FPC2") (pin "14") (pinfunction "14_14") (pintype "passive"))
      (node (ref "FPC4") (pin "19") (pinfunction "19_19") (pintype "passive"))
      (node (ref "U1") (pin "126") (pinfunction "IO,_DIFFIO_T12n_126") (pintype "bidirectional"))
    )
    (net (code "58") (name "/IO127") (class "Default")
      (node (ref "FPC2") (pin "13") (pinfunction "13_13") (pintype "passive"))
      (node (ref "FPC4") (pin "20") (pinfunction "20_20") (pintype "passive"))
      (node (ref "U1") (pin "127") (pinfunction "IO,_DIFFIO_T12p_127") (pintype "bidirectional"))
    )
    (net (code "59") (name "/IO128") (class "Default")
      (node (ref "FPC2") (pin "12") (pinfunction "12_12") (pintype "passive"))
      (node (ref "FPC4") (pin "21") (pinfunction "21_21") (pintype "passive"))
      (node (ref "U1") (pin "128") (pinfunction "IO,_DIFFIO_T11n_128") (pintype "bidirectional"))
    )
    (net (code "60") (name "/IO129") (class "Default")
      (node (ref "FPC2") (pin "11") (pinfunction "11_11") (pintype "passive"))
      (node (ref "FPC4") (pin "22") (pinfunction "22_22") (pintype "passive"))
      (node (ref "U1") (pin "129") (pinfunction "IO,_DIFFIO_T11p_129") (pintype "bidirectional"))
    )
    (net (code "61") (name "/IO132") (class "Default")
      (node (ref "FPC2") (pin "10") (pinfunction "10_10") (pintype "passive"))
      (node (ref "FPC4") (pin "23") (pinfunction "23_23") (pintype "passive"))
      (node (ref "U1") (pin "132") (pinfunction "IO,_DIFFIO_T10n,_(DATA2),_(DQ1T)_132") (pintype "bidirectional"))
    )
    (net (code "62") (name "/IO133") (class "Default")
      (node (ref "FPC2") (pin "9") (pinfunction "9_9") (pintype "passive"))
      (node (ref "FPC4") (pin "24") (pinfunction "24_24") (pintype "passive"))
      (node (ref "U1") (pin "133") (pinfunction "IO,_DIFFIO_T10p,_(DATA3),_(DQ1T)_133") (pintype "bidirectional"))
    )
    (net (code "63") (name "/IO135") (class "Default")
      (node (ref "FPC2") (pin "8") (pinfunction "8_8") (pintype "passive"))
      (node (ref "FPC4") (pin "25") (pinfunction "25_25") (pintype "passive"))
      (node (ref "U1") (pin "135") (pinfunction "IO,_DIFFIO_T8n,_(DQ1T)_135") (pintype "bidirectional"))
    )
    (net (code "64") (name "/IO136") (class "Default")
      (node (ref "FPC2") (pin "7") (pinfunction "7_7") (pintype "passive"))
      (node (ref "FPC4") (pin "26") (pinfunction "26_26") (pintype "passive"))
      (node (ref "U1") (pin "136") (pinfunction "IO,_VREFB8N0_136") (pintype "bidirectional"))
    )
    (net (code "65") (name "/IO137") (class "Default")
      (node (ref "FPC2") (pin "6") (pinfunction "6_6") (pintype "passive"))
      (node (ref "FPC4") (pin "27") (pinfunction "27_27") (pintype "passive"))
      (node (ref "U1") (pin "137") (pinfunction "IO,_(DATA5),_(DQ1T)_137") (pintype "bidirectional"))
    )
    (net (code "66") (name "/IO138") (class "Default")
      (node (ref "FPC2") (pin "5") (pinfunction "5_5") (pintype "passive"))
      (node (ref "FPC4") (pin "28") (pinfunction "28_28") (pintype "passive"))
      (node (ref "U1") (pin "138") (pinfunction "IO,_(DATA6)_138") (pintype "bidirectional"))
    )
    (net (code "67") (name "/IO141") (class "Default")
      (node (ref "FPC2") (pin "4") (pinfunction "4_4") (pintype "passive"))
      (node (ref "FPC4") (pin "29") (pinfunction "29_29") (pintype "passive"))
      (node (ref "U1") (pin "141") (pinfunction "IO,_DIFFIO_T5p_141") (pintype "bidirectional"))
    )
    (net (code "68") (name "/IO142") (class "Default")
      (node (ref "FPC2") (pin "3") (pinfunction "3_3") (pintype "passive"))
      (node (ref "FPC4") (pin "30") (pinfunction "30_30") (pintype "passive"))
      (node (ref "U1") (pin "142") (pinfunction "IO,_DIFFIO_T2p,_(DQS1T/CQ1T#,DPCLK7)_142") (pintype "bidirectional"))
    )
    (net (code "69") (name "/IO143") (class "Default")
      (node (ref "FPC2") (pin "2") (pinfunction "2_2") (pintype "passive"))
      (node (ref "FPC4") (pin "31") (pinfunction "31_31") (pintype "passive"))
      (node (ref "U1") (pin "143") (pinfunction "IO,_DIFFIO_T1n,_(DQ1T)_143") (pintype "bidirectional"))
    )
    (net (code "70") (name "/IO144") (class "Default")
      (node (ref "FPC2") (pin "1") (pinfunction "1_1") (pintype "passive"))
      (node (ref "FPC4") (pin "32") (pinfunction "32_32") (pintype "passive"))
      (node (ref "U1") (pin "144") (pinfunction "IO,_DIFFIO_T1p,_(DM1T)_144") (pintype "bidirectional"))
    )
    (net (code "71") (name "/KEY1") (class "Default")
      (node (ref "R19") (pin "1") (pinfunction "1_1") (pintype "passive"))
      (node (ref "S1") (pin "1") (pinfunction "1_1") (pintype "passive"))
      (node (ref "U1") (pin "89") (pinfunction "CLK6,_DIFFCLK_3p_89") (pintype "input"))
    )
    (net (code "72") (name "/KEY2") (class "Default")
      (node (ref "R20") (pin "1") (pinfunction "1_1") (pintype "passive"))
      (node (ref "S2") (pin "1") (pinfunction "1_1") (pintype "passive"))
      (node (ref "U1") (pin "90") (pinfunction "CLK5,_DIFFCLK_2n_90") (pintype "input"))
    )
    (net (code "73") (name "/LED1") (class "Default")
      (node (ref "D1") (pin "2") (pinfunction "K_2") (pintype "passive"))
      (node (ref "U1") (pin "76") (pinfunction "IO,_RUP3_76") (pintype "bidirectional"))
    )
    (net (code "74") (name "/LED2") (class "Default")
      (node (ref "D2") (pin "2") (pinfunction "K_2") (pintype "passive"))
      (node (ref "U1") (pin "77") (pinfunction "IO,_RDN3_77") (pintype "bidirectional"))
    )
    (net (code "75") (name "/RX") (class "Default")
      (node (ref "D4") (pin "2") (pinfunction "K_2") (pintype "passive"))
      (node (ref "P2") (pin "3") (pinfunction "3_3") (pintype "passive"))
      (node (ref "U1") (pin "87") (pinfunction "IO,_DIFFIO_R7p,_(DEV_CLRn)_87") (pintype "bidirectional"))
      (node (ref "U7") (pin "2") (pinfunction "TXD_2") (pintype "passive"))
    )
    (net (code "76") (name "/TCK") (class "Default")
      (node (ref "J1") (pin "1") (pinfunction "1_1") (pintype "passive"))
      (node (ref "R14") (pin "1") (pinfunction "1_1") (pintype "passive"))
      (node (ref "U1") (pin "16") (pinfunction "TCK_16") (pintype "input"))
    )
    (net (code "77") (name "/TDI") (class "Default")
      (node (ref "J1") (pin "9") (pinfunction "9_9") (pintype "passive"))
      (node (ref "R16") (pin "1") (pinfunction "1_1") (pintype "passive"))
      (node (ref "U1") (pin "15") (pinfunction "TDI_15") (pintype "input"))
    )
    (net (code "78") (name "/TDO") (class "Default")
      (node (ref "J1") (pin "3") (pinfunction "3_3") (pintype "passive"))
      (node (ref "R17") (pin "1") (pinfunction "1_1") (pintype "passive"))
      (node (ref "U1") (pin "20") (pinfunction "TDO_20") (pintype "output"))
    )
    (net (code "79") (name "/TMS") (class "Default")
      (node (ref "J1") (pin "5") (pinfunction "5_5") (pintype "passive"))
      (node (ref "R15") (pin "1") (pinfunction "1_1") (pintype "passive"))
      (node (ref "U1") (pin "18") (pinfunction "TMS_18") (pintype "input"))
    )
    (net (code "80") (name "/TX") (class "Default")
      (node (ref "D3") (pin "2") (pinfunction "K_2") (pintype "passive"))
      (node (ref "P2") (pin "2") (pinfunction "2_2") (pintype "passive"))
      (node (ref "U1") (pin "86") (pinfunction "IO,_DIFFIO_R7n,_(DEV_OE)_86") (pintype "bidirectional"))
      (node (ref "U7") (pin "3") (pinfunction "RXD_3") (pintype "passive"))
    )
    (net (code "81") (name "/nCS") (class "Default")
      (node (ref "U1") (pin "8") (pinfunction "IO,_DIFFIO_L2p,_(FLASH_nCE,nCSO)_8") (pintype "bidirectional"))
      (node (ref "U6") (pin "1") (pinfunction "1_1") (pintype "passive"))
    )
    (net (code "82") (name "1_2V") (class "Default")
      (node (ref "C18") (pin "2") (pinfunction "2_2") (pintype "passive"))
      (node (ref "C19") (pin "2") (pinfunction "2_2") (pintype "passive"))
      (node (ref "C20") (pin "2") (pinfunction "2_2") (pintype "passive"))
      (node (ref "C21") (pin "2") (pinfunction "2_2") (pintype "passive"))
      (node (ref "C22") (pin "2") (pinfunction "2_2") (pintype "passive"))
      (node (ref "C23") (pin "2") (pinfunction "2_2") (pintype "passive"))
      (node (ref "U1") (pin "102") (pinfunction "VCCINT_102") (pintype "power_in"))
      (node (ref "U1") (pin "109") (pinfunction "VCCD_PLL2_109") (pintype "power_in"))
      (node (ref "U1") (pin "116") (pinfunction "VCCINT_116") (pintype "power_in"))
      (node (ref "U1") (pin "134") (pinfunction "VCCINT_134") (pintype "power_in"))
      (node (ref "U1") (pin "29") (pinfunction "VCCINT_29") (pintype "power_in"))
      (node (ref "U1") (pin "37") (pinfunction "VCCD_PLL1_37") (pintype "power_in"))
      (node (ref "U1") (pin "45") (pinfunction "VCCINT_45") (pintype "power_in"))
      (node (ref "U1") (pin "5") (pinfunction "VCCINT_5") (pintype "power_in"))
      (node (ref "U1") (pin "61") (pinfunction "VCCINT_61") (pintype "power_in"))
      (node (ref "U1") (pin "78") (pinfunction "VCCINT_78") (pintype "power_in"))
      (node (ref "U5") (pin "2") (pinfunction "VOUT_2") (pintype "passive"))
    )
    (net (code "83") (name "2_5V") (class "Default")
      (node (ref "C10") (pin "2") (pinfunction "2_2") (pintype "passive"))
      (node (ref "C9") (pin "2") (pinfunction "2_2") (pintype "passive"))
      (node (ref "U1") (pin "107") (pinfunction "VCCA2_107") (pintype "power_in"))
      (node (ref "U1") (pin "35") (pinfunction "VCCA1_35") (pintype "power_in"))
      (node (ref "U1") (pin "96") (pinfunction "MSEL1_96") (pintype "input"))
      (node (ref "U4") (pin "2") (pinfunction "VOUT_2") (pintype "passive"))
    )
    (net (code "84") (name "3_3V") (class "Default")
      (node (ref "C11") (pin "2") (pinfunction "2_2") (pintype "passive"))
      (node (ref "C12") (pin "2") (pinfunction "2_2") (pintype "passive"))
      (node (ref "C13") (pin "2") (pinfunction "2_2") (pintype "passive"))
      (node (ref "C14") (pin "2") (pinfunction "2_2") (pintype "passive"))
      (node (ref "C15") (pin "2") (pinfunction "2_2") (pintype "passive"))
      (node (ref "C16") (pin "2") (pinfunction "2_2") (pintype "passive"))
      (node (ref "C17") (pin "2") (pinfunction "2_2") (pintype "passive"))
      (node (ref "C25") (pin "2") (pinfunction "2_2") (pintype "passive"))
      (node (ref "C26") (pin "2") (pinfunction "2_2") (pintype "passive"))
      (node (ref "J1") (pin "4") (pinfunction "4_4") (pintype "passive"))
      (node (ref "P2") (pin "1") (pinfunction "1_1") (pintype "passive"))
      (node (ref "R1") (pin "2") (pinfunction "2_2") (pintype "passive"))
      (node (ref "R15") (pin "2") (pinfunction "2_2") (pintype "passive"))
      (node (ref "R16") (pin "2") (pinfunction "2_2") (pintype "passive"))
      (node (ref "R17") (pin "2") (pinfunction "2_2") (pintype "passive"))
      (node (ref "R18") (pin "2") (pinfunction "2_2") (pintype "passive"))
      (node (ref "R19") (pin "2") (pinfunction "2_2") (pintype "passive"))
      (node (ref "R2") (pin "2") (pinfunction "2_2") (pintype "passive"))
      (node (ref "R20") (pin "2") (pinfunction "2_2") (pintype "passive"))
      (node (ref "R21") (pin "2") (pinfunction "2_2") (pintype "passive"))
      (node (ref "R22") (pin "1") (pinfunction "1_1") (pintype "passive"))
      (node (ref "R23") (pin "1") (pinfunction "1_1") (pintype "passive"))
      (node (ref "R3") (pin "2") (pinfunction "2_2") (pintype "passive"))
      (node (ref "U1") (pin "117") (pinfunction "VCCIO7_117") (pintype "power_in"))
      (node (ref "U1") (pin "122") (pinfunction "VCCIO7_122") (pintype "power_in"))
      (node (ref "U1") (pin "130") (pinfunction "VCCIO8_130") (pintype "power_in"))
      (node (ref "U1") (pin "139") (pinfunction "VCCIO8_139") (pintype "power_in"))
      (node (ref "U1") (pin "17") (pinfunction "VCCIO1_17") (pintype "power_in"))
      (node (ref "U1") (pin "26") (pinfunction "VCCIO2_26") (pintype "power_in"))
      (node (ref "U1") (pin "40") (pinfunction "VCCIO3_40") (pintype "power_in"))
      (node (ref "U1") (pin "47") (pinfunction "VCCIO3_47") (pintype "power_in"))
      (node (ref "U1") (pin "56") (pinfunction "VCCIO4_56") (pintype "power_in"))
      (node (ref "U1") (pin "62") (pinfunction "VCCIO4_62") (pintype "power_in"))
      (node (ref "U1") (pin "81") (pinfunction "VCCIO5_81") (pintype "power_in"))
      (node (ref "U1") (pin "93") (pinfunction "VCCIO6_93") (pintype "power_in"))
      (node (ref "U3") (pin "2") (pinfunction "VOUT_2") (pintype "passive"))
      (node (ref "U6") (pin "3") (pinfunction "3_3") (pintype "passive"))
      (node (ref "U6") (pin "7") (pinfunction "7_7") (pintype "passive"))
      (node (ref "U6") (pin "8") (pinfunction "8_8") (pintype "passive"))
      (node (ref "U7") (pin "16") (pinfunction "VCC_16") (pintype "passive"))
      (node (ref "U7") (pin "4") (pinfunction "V3_4") (pintype "passive"))
      (node (ref "Y1") (pin "4") (pinfunction "VCC_4") (pintype "power_in"))
    )
    (net (code "85") (name "5V") (class "Default")
      (node (ref "Rz") (pin "2") (pinfunction "2_2") (pintype "passive"))
      (node (ref "SW1") (pin "2") (pinfunction "2_2") (pintype "passive"))
      (node (ref "SW1") (pin "5") (pinfunction "5_5") (pintype "passive"))
      (node (ref "U3") (pin "3") (pinfunction "VIN_3") (pintype "passive"))
      (node (ref "U4") (pin "3") (pinfunction "VIN_3") (pintype "passive"))
      (node (ref "U5") (pin "3") (pinfunction "VIN_3") (pintype "passive"))
    )
    (net (code "86") (name "5V_DC") (class "Default")
      (node (ref "C4") (pin "2") (pinfunction "2_2") (pintype "passive"))
      (node (ref "C5") (pin "2") (pinfunction "2_2") (pintype "passive"))
      (node (ref "L1") (pin "1") (pinfunction "1_1") (pintype "passive"))
      (node (ref "P1") (pin "3") (pinfunction "3_3") (pintype "passive"))
      (node (ref "R6") (pin "1") (pinfunction "1_1") (pintype "passive"))
    )
    (net (code "87") (name "5V_USB") (class "Default")
      (node (ref "C8") (pin "2") (pinfunction "2_2") (pintype "passive"))
      (node (ref "P1") (pin "1") (pinfunction "1_1") (pintype "passive"))
      (node (ref "USB1") (pin "1") (pinfunction "V+_1") (pintype "passive"))
    )
    (net (code "88") (name "5V_W") (class "Default")
      (node (ref "P1") (pin "2") (pinfunction "2_2") (pintype "passive"))
      (node (ref "SW1") (pin "3") (pinfunction "3_3") (pintype "passive"))
      (node (ref "SW1") (pin "6") (pinfunction "6_6") (pintype "passive"))
    )
    (net (code "89") (name "GND") (class "Default")
      (node (ref "C10") (pin "1") (pinfunction "1_1") (pintype "passive"))
      (node (ref "C11") (pin "1") (pinfunction "1_1") (pintype "passive"))
      (node (ref "C12") (pin "1") (pinfunction "1_1") (pintype "passive"))
      (node (ref "C13") (pin "1") (pinfunction "1_1") (pintype "passive"))
      (node (ref "C14") (pin "1") (pinfunction "1_1") (pintype "passive"))
      (node (ref "C15") (pin "1") (pinfunction "1_1") (pintype "passive"))
      (node (ref "C16") (pin "1") (pinfunction "1_1") (pintype "passive"))
      (node (ref "C17") (pin "1") (pinfunction "1_1") (pintype "passive"))
      (node (ref "C18") (pin "1") (pinfunction "1_1") (pintype "passive"))
      (node (ref "C19") (pin "1") (pinfunction "1_1") (pintype "passive"))
      (node (ref "C20") (pin "1") (pinfunction "1_1") (pintype "passive"))
      (node (ref "C21") (pin "1") (pinfunction "1_1") (pintype "passive"))
      (node (ref "C22") (pin "1") (pinfunction "1_1") (pintype "passive"))
      (node (ref "C23") (pin "1") (pinfunction "1_1") (pintype "passive"))
      (node (ref "C25") (pin "1") (pinfunction "1_1") (pintype "passive"))
      (node (ref "C26") (pin "1") (pinfunction "1_1") (pintype "passive"))
      (node (ref "C27") (pin "1") (pinfunction "1_1") (pintype "passive"))
      (node (ref "C28") (pin "1") (pinfunction "1_1") (pintype "passive"))
      (node (ref "C8") (pin "1") (pinfunction "1_1") (pintype "passive"))
      (node (ref "C9") (pin "1") (pinfunction "1_1") (pintype "passive"))
      (node (ref "J1") (pin "10") (pinfunction "10_10") (pintype "passive"))
      (node (ref "J1") (pin "2") (pinfunction "2_2") (pintype "passive"))
      (node (ref "P2") (pin "4") (pinfunction "4_4") (pintype "passive"))
      (node (ref "R10") (pin "1") (pinfunction "1_1") (pintype "passive"))
      (node (ref "R12") (pin "1") (pinfunction "1_1") (pintype "passive"))
      (node (ref "R13") (pin "1") (pinfunction "1_1") (pintype "passive"))
      (node (ref "R14") (pin "2") (pinfunction "2_2") (pintype "passive"))
      (node (ref "S1") (pin "2") (pinfunction "2_2") (pintype "passive"))
      (node (ref "S2") (pin "2") (pinfunction "2_2") (pintype "passive"))
      (node (ref "U1") (pin "108") (pinfunction "GNDA2_108") (pintype "power_in"))
      (node (ref "U1") (pin "118") (pinfunction "GND_118") (pintype "power_in"))
      (node (ref "U1") (pin "123") (pinfunction "GND_123") (pintype "power_in"))
      (node (ref "U1") (pin "131") (pinfunction "GND_131") (pintype "power_in"))
      (node (ref "U1") (pin "140") (pinfunction "GND_140") (pintype "power_in"))
      (node (ref "U1") (pin "145") (pinfunction "GND_145") (pintype "power_in"))
      (node (ref "U1") (pin "19") (pinfunction "GND_19") (pintype "power_in"))
      (node (ref "U1") (pin "22") (pinfunction "GND_22") (pintype "power_in"))
      (node (ref "U1") (pin "27") (pinfunction "GND_27") (pintype "power_in"))
      (node (ref "U1") (pin "36") (pinfunction "GNDA1_36") (pintype "power_in"))
      (node (ref "U1") (pin "4") (pinfunction "GND_4") (pintype "power_in"))
      (node (ref "U1") (pin "41") (pinfunction "GND_41") (pintype "power_in"))
      (node (ref "U1") (pin "48") (pinfunction "GND_48") (pintype "power_in"))
      (node (ref "U1") (pin "57") (pinfunction "GND_57") (pintype "power_in"))
      (node (ref "U1") (pin "63") (pinfunction "GND_63") (pintype "power_in"))
      (node (ref "U1") (pin "79") (pinfunction "GND_79") (pintype "power_in"))
      (node (ref "U1") (pin "82") (pinfunction "GND_82") (pintype "power_in"))
      (node (ref "U1") (pin "94") (pinfunction "MSEL0_94") (pintype "input"))
      (node (ref "U1") (pin "95") (pinfunction "GND_95") (pintype "power_in"))
      (node (ref "U1") (pin "97") (pinfunction "MSEL2_97") (pintype "input"))
      (node (ref "U3") (pin "1") (pinfunction "GND_1") (pintype "passive"))
      (node (ref "U4") (pin "1") (pinfunction "GND_1") (pintype "passive"))
      (node (ref "U5") (pin "1") (pinfunction "GND_1") (pintype "passive"))
      (node (ref "U6") (pin "4") (pinfunction "4_4") (pintype "passive"))
      (node (ref "U7") (pin "1") (pinfunction "GND_1") (pintype "passive"))
      (node (ref "USB1") (pin "0") (pinfunction "MTN_0") (pintype "passive"))
      (node (ref "USB1") (pin "4") (pinfunction "ID_4") (pintype "passive"))
      (node (ref "USB1") (pin "5") (pinfunction "V-_5") (pintype "passive"))
      (node (ref "Y1") (pin "2") (pinfunction "GND_2") (pintype "power_in"))
    )
    (net (code "90") (name "Net-(C7-Pad2)") (class "Default")
      (node (ref "C7") (pin "2") (pinfunction "2_2") (pintype "passive"))
      (node (ref "R11") (pin "2") (pinfunction "2_2") (pintype "passive"))
    )
    (net (code "91") (name "Net-(D1-A)") (class "Default")
      (node (ref "D1") (pin "1") (pinfunction "A_1") (pintype "passive"))
      (node (ref "R18") (pin "1") (pinfunction "1_1") (pintype "passive"))
    )
    (net (code "92") (name "Net-(D2-A)") (class "Default")
      (node (ref "D2") (pin "1") (pinfunction "A_1") (pintype "passive"))
      (node (ref "R21") (pin "1") (pinfunction "1_1") (pintype "passive"))
    )
    (net (code "93") (name "Net-(D3-A)") (class "Default")
      (node (ref "D3") (pin "1") (pinfunction "A_1") (pintype "passive"))
      (node (ref "R22") (pin "2") (pinfunction "2_2") (pintype "passive"))
    )
    (net (code "94") (name "Net-(D4-A)") (class "Default")
      (node (ref "D4") (pin "1") (pinfunction "A_1") (pintype "passive"))
      (node (ref "R23") (pin "2") (pinfunction "2_2") (pintype "passive"))
    )
    (net (code "95") (name "Net-(Dz-A)") (class "Default")
      (node (ref "Dz") (pin "1") (pinfunction "A_1") (pintype "passive"))
      (node (ref "Rz") (pin "1") (pinfunction "1_1") (pintype "passive"))
    )
    (net (code "96") (name "Net-(R6-Pad2)") (class "Default")
      (node (ref "R6") (pin "2") (pinfunction "2_2") (pintype "passive"))
      (node (ref "R8") (pin "1") (pinfunction "1_1") (pintype "passive"))
      (node (ref "R9") (pin "1") (pinfunction "1_1") (pintype "passive"))
    )
    (net (code "97") (name "Net-(U1I-CLK2,_DIFFCLK_1p)") (class "Default")
      (node (ref "R5") (pin "1") (pinfunction "1_1") (pintype "passive"))
      (node (ref "U1") (pin "24") (pinfunction "CLK2,_DIFFCLK_1p_24") (pintype "input"))
    )
    (net (code "98") (name "Net-(U1J-CONF_DONE)") (class "Default")
      (node (ref "R3") (pin "1") (pinfunction "1_1") (pintype "passive"))
      (node (ref "U1") (pin "92") (pinfunction "CONF_DONE_92") (pintype "bidirectional"))
    )
    (net (code "99") (name "Net-(U1J-nCE)") (class "Default")
      (node (ref "R10") (pin "2") (pinfunction "2_2") (pintype "passive"))
      (node (ref "U1") (pin "21") (pinfunction "nCE_21") (pintype "input"))
    )
    (net (code "100") (name "Net-(U1J-nCONFIG)") (class "Default")
      (node (ref "R2") (pin "1") (pinfunction "1_1") (pintype "passive"))
      (node (ref "U1") (pin "14") (pinfunction "nCONFIG_14") (pintype "input"))
    )
    (net (code "101") (name "Net-(U1J-nSTATUS)") (class "Default")
      (node (ref "R1") (pin "1") (pinfunction "1_1") (pintype "passive"))
      (node (ref "U1") (pin "9") (pinfunction "nSTATUS_9") (pintype "bidirectional"))
    )
    (net (code "102") (name "Net-(U2-AAM)") (class "Default")
      (node (ref "R7") (pin "2") (pinfunction "2_2") (pintype "passive"))
      (node (ref "U2") (pin "1") (pinfunction "AAM_1") (pintype "passive"))
    )
    (net (code "103") (name "Net-(U2-BST)") (class "Default")
      (node (ref "R11") (pin "1") (pinfunction "1_1") (pintype "passive"))
      (node (ref "U2") (pin "5") (pinfunction "BST_5") (pintype "passive"))
    )
    (net (code "104") (name "Net-(U2-EN{slash}SYNC)") (class "Default")
      (node (ref "R4") (pin "1") (pinfunction "1_1") (pintype "passive"))
      (node (ref "U2") (pin "6") (pinfunction "EN/SYNC_6") (pintype "passive"))
    )
    (net (code "105") (name "Net-(U2-FB)") (class "Default")
      (node (ref "R8") (pin "2") (pinfunction "2_2") (pintype "passive"))
      (node (ref "U2") (pin "8") (pinfunction "FB_8") (pintype "passive"))
    )
    (net (code "106") (name "Net-(U2-SW)") (class "Default")
      (node (ref "C7") (pin "1") (pinfunction "1_1") (pintype "passive"))
      (node (ref "L1") (pin "2") (pinfunction "2_2") (pintype "passive"))
      (node (ref "U2") (pin "3") (pinfunction "SW_3") (pintype "passive"))
    )
    (net (code "107") (name "Net-(U2-VCC)") (class "Default")
      (node (ref "C6") (pin "2") (pinfunction "2_2") (pintype "passive"))
      (node (ref "R7") (pin "1") (pinfunction "1_1") (pintype "passive"))
      (node (ref "U2") (pin "7") (pinfunction "VCC_7") (pintype "passive"))
    )
    (net (code "108") (name "Net-(U7-XI)") (class "Default")
      (node (ref "C27") (pin "2") (pinfunction "2_2") (pintype "passive"))
      (node (ref "U7") (pin "7") (pinfunction "XI_7") (pintype "passive"))
      (node (ref "Y2") (pin "1") (pinfunction "OSC1_1") (pintype "passive"))
    )
    (net (code "109") (name "Net-(U7-XO)") (class "Default")
      (node (ref "C28") (pin "2") (pinfunction "2_2") (pintype "passive"))
      (node (ref "U7") (pin "8") (pinfunction "XO_8") (pintype "passive"))
      (node (ref "Y2") (pin "2") (pinfunction "OSC2_2") (pintype "passive"))
    )
    (net (code "110") (name "PGND") (class "Default")
      (node (ref "C1") (pin "2") (pinfunction "2_2") (pintype "passive"))
      (node (ref "C2") (pin "2") (pinfunction "2_2") (pintype "passive"))
      (node (ref "C3") (pin "1") (pinfunction "1_1") (pintype "passive"))
      (node (ref "C4") (pin "1") (pinfunction "1_1") (pintype "passive"))
      (node (ref "C5") (pin "1") (pinfunction "1_1") (pintype "passive"))
      (node (ref "C6") (pin "1") (pinfunction "1_1") (pintype "passive"))
      (node (ref "Dz") (pin "2") (pinfunction "K_2") (pintype "passive"))
      (node (ref "JP1") (pin "1") (pinfunction "1_1") (pintype "passive"))
      (node (ref "JP1") (pin "4") (pinfunction "4_4") (pintype "passive"))
      (node (ref "R12") (pin "2") (pinfunction "2_2") (pintype "passive"))
      (node (ref "R13") (pin "2") (pinfunction "2_2") (pintype "passive"))
      (node (ref "R9") (pin "2") (pinfunction "2_2") (pintype "passive"))
      (node (ref "U2") (pin "4") (pinfunction "GND_4") (pintype "passive"))
    )
    (net (code "111") (name "VIN") (class "Default")
      (node (ref "C1") (pin "1") (pinfunction "1_1") (pintype "passive"))
      (node (ref "C2") (pin "1") (pinfunction "1_1") (pintype "passive"))
      (node (ref "C3") (pin "2") (pinfunction "2_2") (pintype "passive"))
      (node (ref "JP1") (pin "2") (pinfunction "2_2") (pintype "passive"))
      (node (ref "JP1") (pin "3") (pinfunction "3_3") (pintype "passive"))
      (node (ref "R4") (pin "2") (pinfunction "2_2") (pintype "passive"))
      (node (ref "U2") (pin "2") (pinfunction "IN_2") (pintype "passive"))
    )
    (net (code "112") (name "unconnected-(FPC1-Pad33)") (class "Default")
      (node (ref "FPC1") (pin "33") (pinfunction "33_33") (pintype "passive"))
    )
    (net (code "113") (name "unconnected-(FPC1-Pad34)") (class "Default")
      (node (ref "FPC1") (pin "34") (pinfunction "34_34") (pintype "passive"))
    )
    (net (code "114") (name "unconnected-(FPC2-Pad33)") (class "Default")
      (node (ref "FPC2") (pin "33") (pinfunction "33_33") (pintype "passive"))
    )
    (net (code "115") (name "unconnected-(FPC2-Pad34)") (class "Default")
      (node (ref "FPC2") (pin "34") (pinfunction "34_34") (pintype "passive"))
    )
    (net (code "116") (name "unconnected-(FPC3-Pad33)") (class "Default")
      (node (ref "FPC3") (pin "33") (pinfunction "33_33") (pintype "passive"))
    )
    (net (code "117") (name "unconnected-(FPC3-Pad34)") (class "Default")
      (node (ref "FPC3") (pin "34") (pinfunction "34_34") (pintype "passive"))
    )
    (net (code "118") (name "unconnected-(FPC4-Pad33)") (class "Default")
      (node (ref "FPC4") (pin "33") (pinfunction "33_33") (pintype "passive"))
    )
    (net (code "119") (name "unconnected-(FPC4-Pad34)") (class "Default")
      (node (ref "FPC4") (pin "34") (pinfunction "34_34") (pintype "passive"))
    )
    (net (code "120") (name "unconnected-(J1-Pad6)") (class "Default")
      (node (ref "J1") (pin "6") (pinfunction "6_6") (pintype "passive"))
    )
    (net (code "121") (name "unconnected-(J1-Pad7)") (class "Default")
      (node (ref "J1") (pin "7") (pinfunction "7_7") (pintype "passive"))
    )
    (net (code "122") (name "unconnected-(J1-Pad8)") (class "Default")
      (node (ref "J1") (pin "8") (pinfunction "8_8") (pintype "passive"))
    )
    (net (code "123") (name "unconnected-(SW1-Pad1)") (class "Default")
      (node (ref "SW1") (pin "1") (pinfunction "1_1") (pintype "passive"))
    )
    (net (code "124") (name "unconnected-(SW1-Pad4)") (class "Default")
      (node (ref "SW1") (pin "4") (pinfunction "4_4") (pintype "passive"))
    )
    (net (code "125") (name "unconnected-(U1A-IO,_DIFFIO_L4n-Pad11)") (class "Default")
      (node (ref "U1") (pin "11") (pinfunction "IO,_DIFFIO_L4n_11") (pintype "bidirectional"))
    )
    (net (code "126") (name "unconnected-(U1A-IO,_DIFFIO_L4p,_(DQS0L{slash}CQ1L,DPCLK0)-Pad10)") (class "Default")
      (node (ref "U1") (pin "10") (pinfunction "IO,_DIFFIO_L4p,_(DQS0L/CQ1L,DPCLK0)_10") (pintype "bidirectional"))
    )
    (net (code "127") (name "unconnected-(U1A-IO,_VREFB1N0-Pad7)") (class "Default")
      (node (ref "U1") (pin "7") (pinfunction "IO,_VREFB1N0_7") (pintype "bidirectional"))
    )
    (net (code "128") (name "unconnected-(U1A-IO-Pad1)") (class "Default")
      (node (ref "U1") (pin "1") (pinfunction "IO_1") (pintype "bidirectional"))
    )
    (net (code "129") (name "unconnected-(U1A-IO-Pad2)") (class "Default")
      (node (ref "U1") (pin "2") (pinfunction "IO_2") (pintype "bidirectional"))
    )
    (net (code "130") (name "unconnected-(U1A-IO-Pad3)") (class "Default")
      (node (ref "U1") (pin "3") (pinfunction "IO_3") (pintype "bidirectional"))
    )
    (net (code "131") (name "unconnected-(U1E-IO,_DIFFIO_R8n-Pad84)") (class "Default")
      (node (ref "U1") (pin "84") (pinfunction "IO,_DIFFIO_R8n_84") (pintype "bidirectional"))
    )
    (net (code "132") (name "unconnected-(U1E-IO,_DIFFIO_R8p,_(DQS1R{slash}CQ1R#,DPCLK4)-Pad85)") (class "Default")
      (node (ref "U1") (pin "85") (pinfunction "IO,_DIFFIO_R8p,_(DQS1R/CQ1R#,DPCLK4)_85") (pintype "bidirectional"))
    )
    (net (code "133") (name "unconnected-(U1E-IO,_VREFB5N0-Pad80)") (class "Default")
      (node (ref "U1") (pin "80") (pinfunction "IO,_VREFB5N0_80") (pintype "bidirectional"))
    )
    (net (code "134") (name "unconnected-(U1E-IO-Pad74)") (class "Default")
      (node (ref "U1") (pin "74") (pinfunction "IO_74") (pintype "bidirectional"))
    )
    (net (code "135") (name "unconnected-(U1E-IO-Pad75)") (class "Default")
      (node (ref "U1") (pin "75") (pinfunction "IO_75") (pintype "bidirectional"))
    )
    (net (code "136") (name "unconnected-(U1E-IO-Pad83)") (class "Default")
      (node (ref "U1") (pin "83") (pinfunction "IO_83") (pintype "bidirectional"))
    )
    (net (code "137") (name "unconnected-(U1F-IO,_DIFFIO_R4n,_(INIT_DONE)-Pad98)") (class "Default")
      (node (ref "U1") (pin "98") (pinfunction "IO,_DIFFIO_R4n,_(INIT_DONE)_98") (pintype "bidirectional"))
    )
    (net (code "138") (name "unconnected-(U1I-CLK1,_DIFFCLK_0n-Pad23)") (class "Default")
      (node (ref "U1") (pin "23") (pinfunction "CLK1,_DIFFCLK_0n_23") (pintype "input"))
    )
    (net (code "139") (name "unconnected-(U1I-CLK3,_DIFFCLK_1n-Pad25)") (class "Default")
      (node (ref "U1") (pin "25") (pinfunction "CLK3,_DIFFCLK_1n_25") (pintype "input"))
    )
    (net (code "140") (name "unconnected-(U1I-CLK4,_DIFFCLK_2p-Pad91)") (class "Default")
      (node (ref "U1") (pin "91") (pinfunction "CLK4,_DIFFCLK_2p_91") (pintype "input"))
    )
    (net (code "141") (name "unconnected-(U1I-CLK7,_DIFFCLK_3n-Pad88)") (class "Default")
      (node (ref "U1") (pin "88") (pinfunction "CLK7,_DIFFCLK_3n_88") (pintype "input"))
    )
    (net (code "142") (name "unconnected-(U3-VOUT-Pad4)") (class "Default")
      (node (ref "U3") (pin "4") (pinfunction "VOUT_4") (pintype "passive"))
    )
    (net (code "143") (name "unconnected-(U4-VOUT-Pad4)") (class "Default")
      (node (ref "U4") (pin "4") (pinfunction "VOUT_4") (pintype "passive"))
    )
    (net (code "144") (name "unconnected-(U5-VOUT-Pad4)") (class "Default")
      (node (ref "U5") (pin "4") (pinfunction "VOUT_4") (pintype "passive"))
    )
    (net (code "145") (name "unconnected-(U7-CTS#-Pad9)") (class "Default")
      (node (ref "U7") (pin "9") (pinfunction "CTS#_9") (pintype "passive"))
    )
    (net (code "146") (name "unconnected-(U7-DCD#-Pad12)") (class "Default")
      (node (ref "U7") (pin "12") (pinfunction "DCD#_12") (pintype "passive"))
    )
    (net (code "147") (name "unconnected-(U7-DSR#-Pad10)") (class "Default")
      (node (ref "U7") (pin "10") (pinfunction "DSR#_10") (pintype "passive"))
    )
    (net (code "148") (name "unconnected-(U7-DTR#-Pad13)") (class "Default")
      (node (ref "U7") (pin "13") (pinfunction "DTR#_13") (pintype "passive"))
    )
    (net (code "149") (name "unconnected-(U7-R232-Pad15)") (class "Default")
      (node (ref "U7") (pin "15") (pinfunction "R232_15") (pintype "passive"))
    )
    (net (code "150") (name "unconnected-(U7-RI-Pad11)") (class "Default")
      (node (ref "U7") (pin "11") (pinfunction "RI_11") (pintype "passive"))
    )
    (net (code "151") (name "unconnected-(U7-RTS#-Pad14)") (class "Default")
      (node (ref "U7") (pin "14") (pinfunction "RTS#_14") (pintype "passive"))
    )
    (net (code "152") (name "unconnected-(Y1-NC-Pad1)") (class "Default")
      (node (ref "Y1") (pin "1") (pinfunction "NC_1") (pintype "passive"))
    )
  )
)
